# IPM_24V_12V.net
KiCad netlist of a schematic drawn in EasyEDA Pro
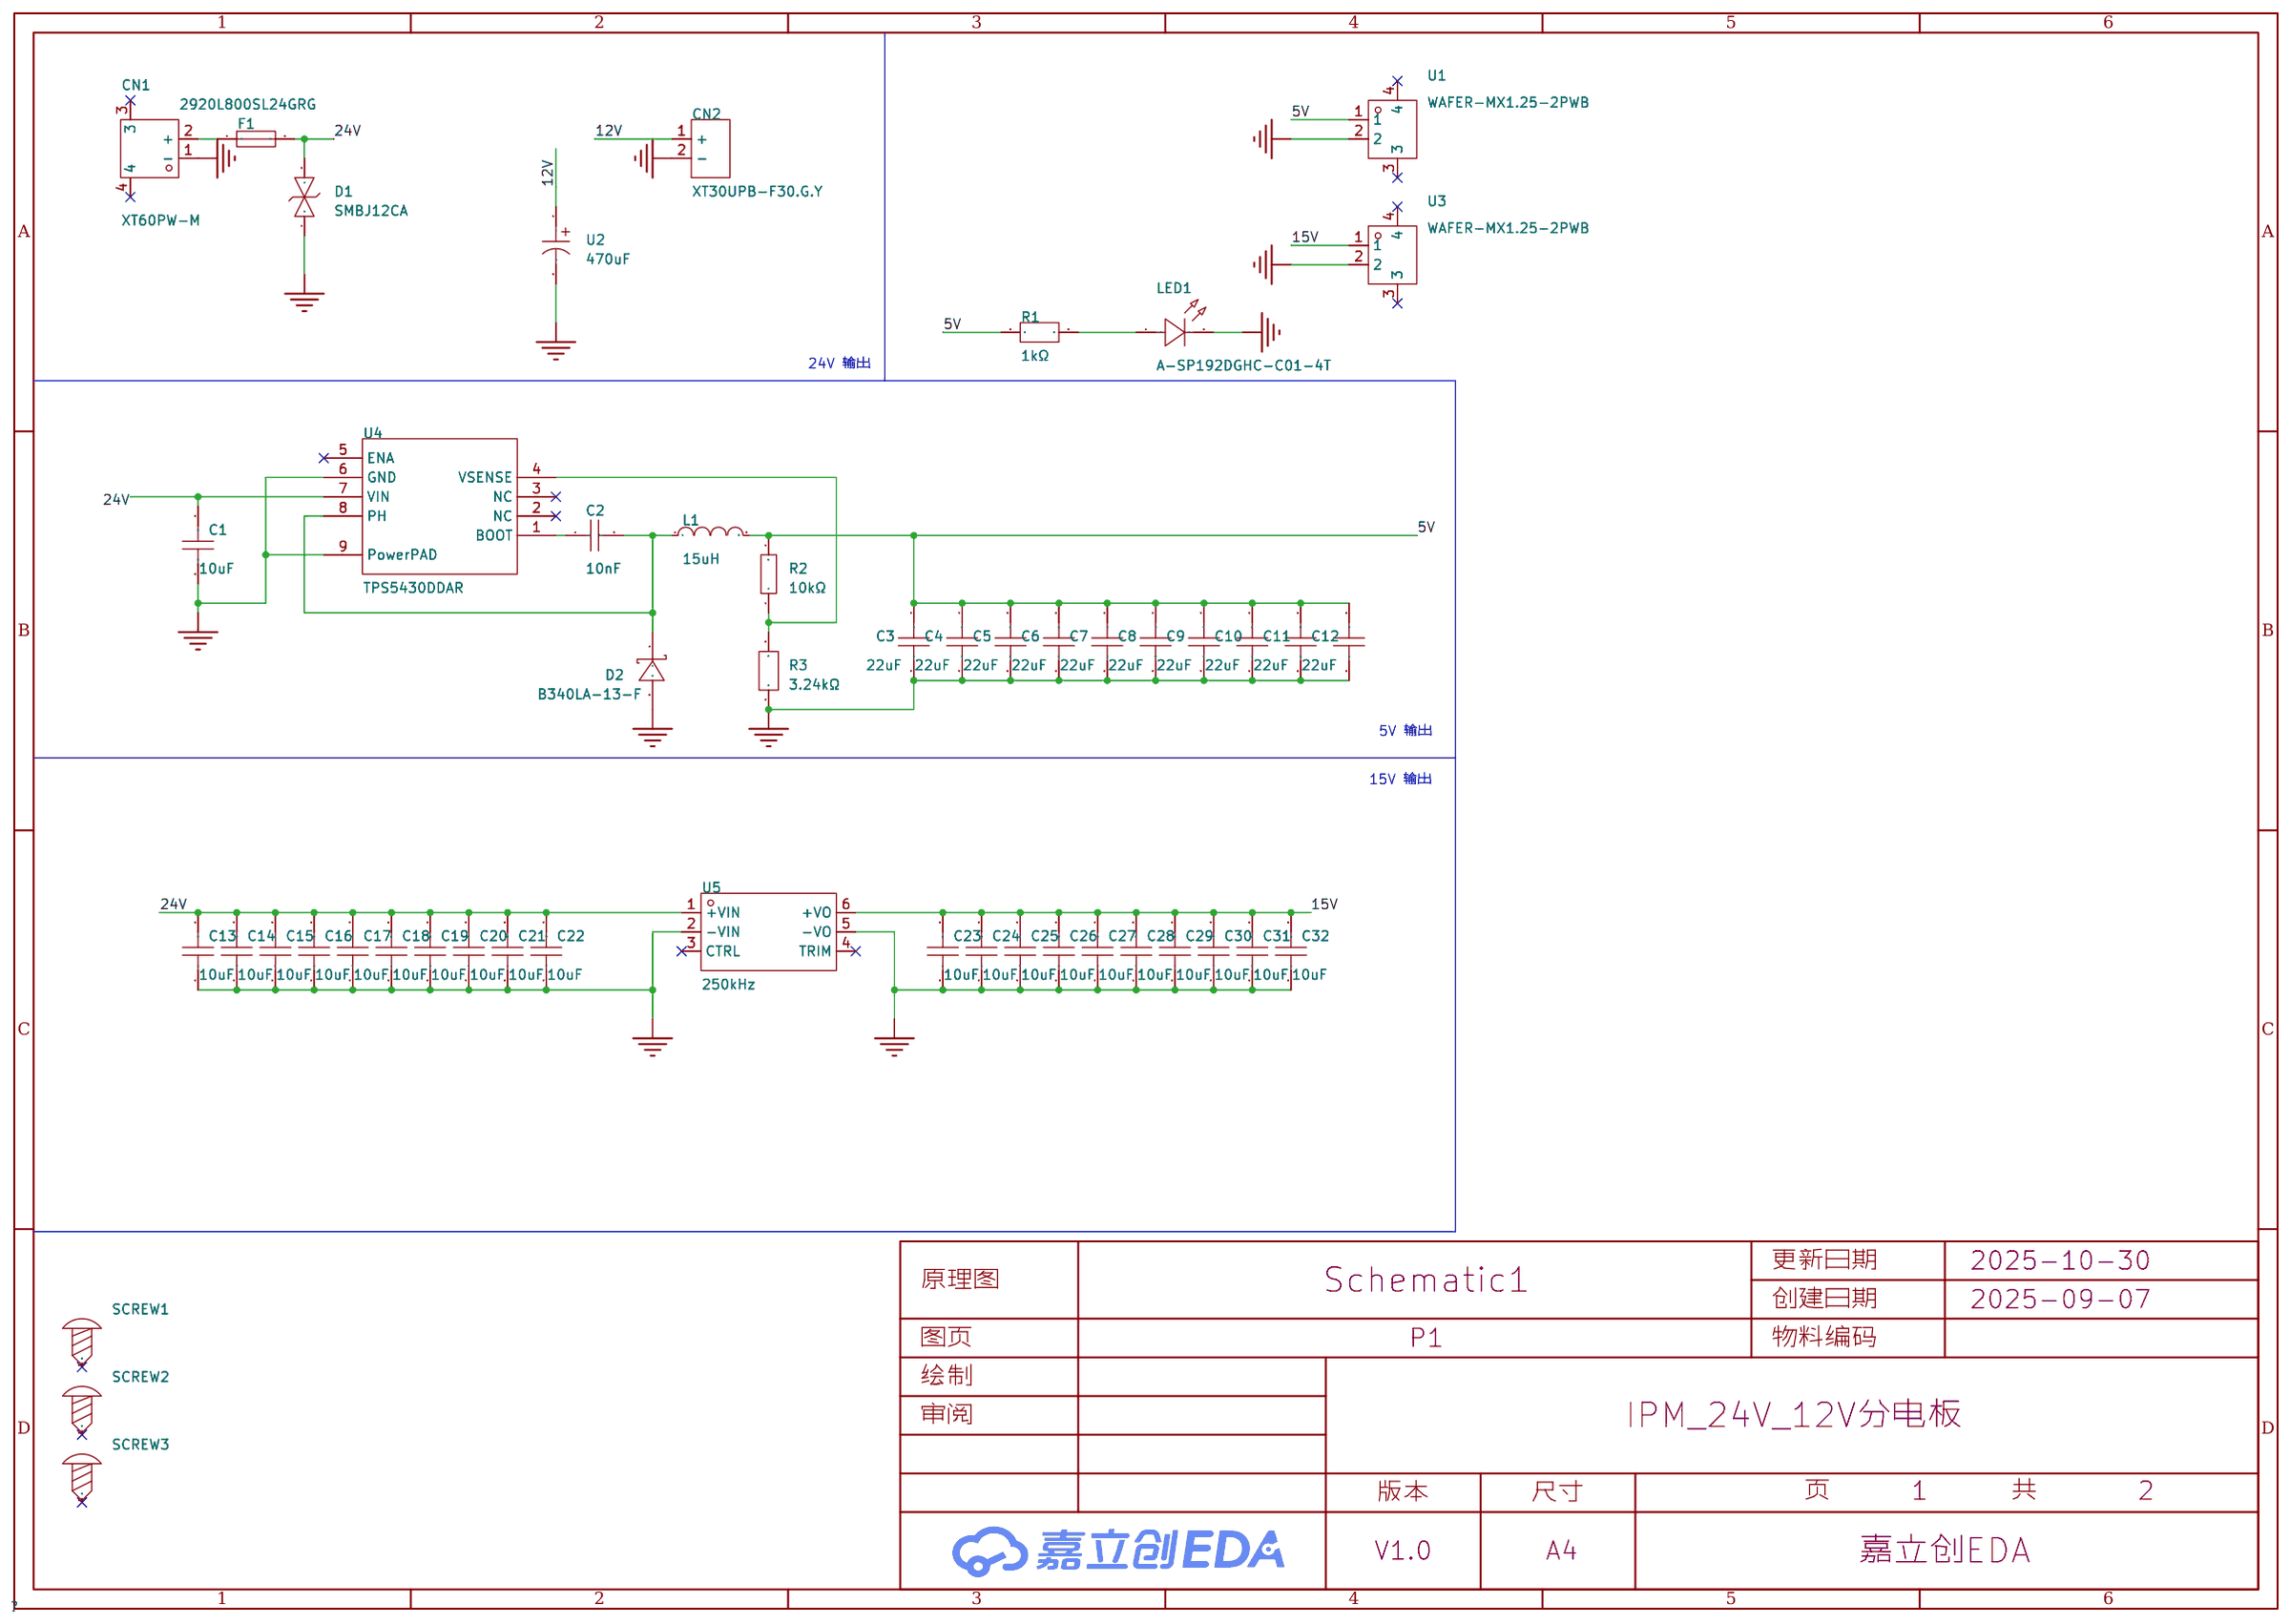
[diagram p0: P1]
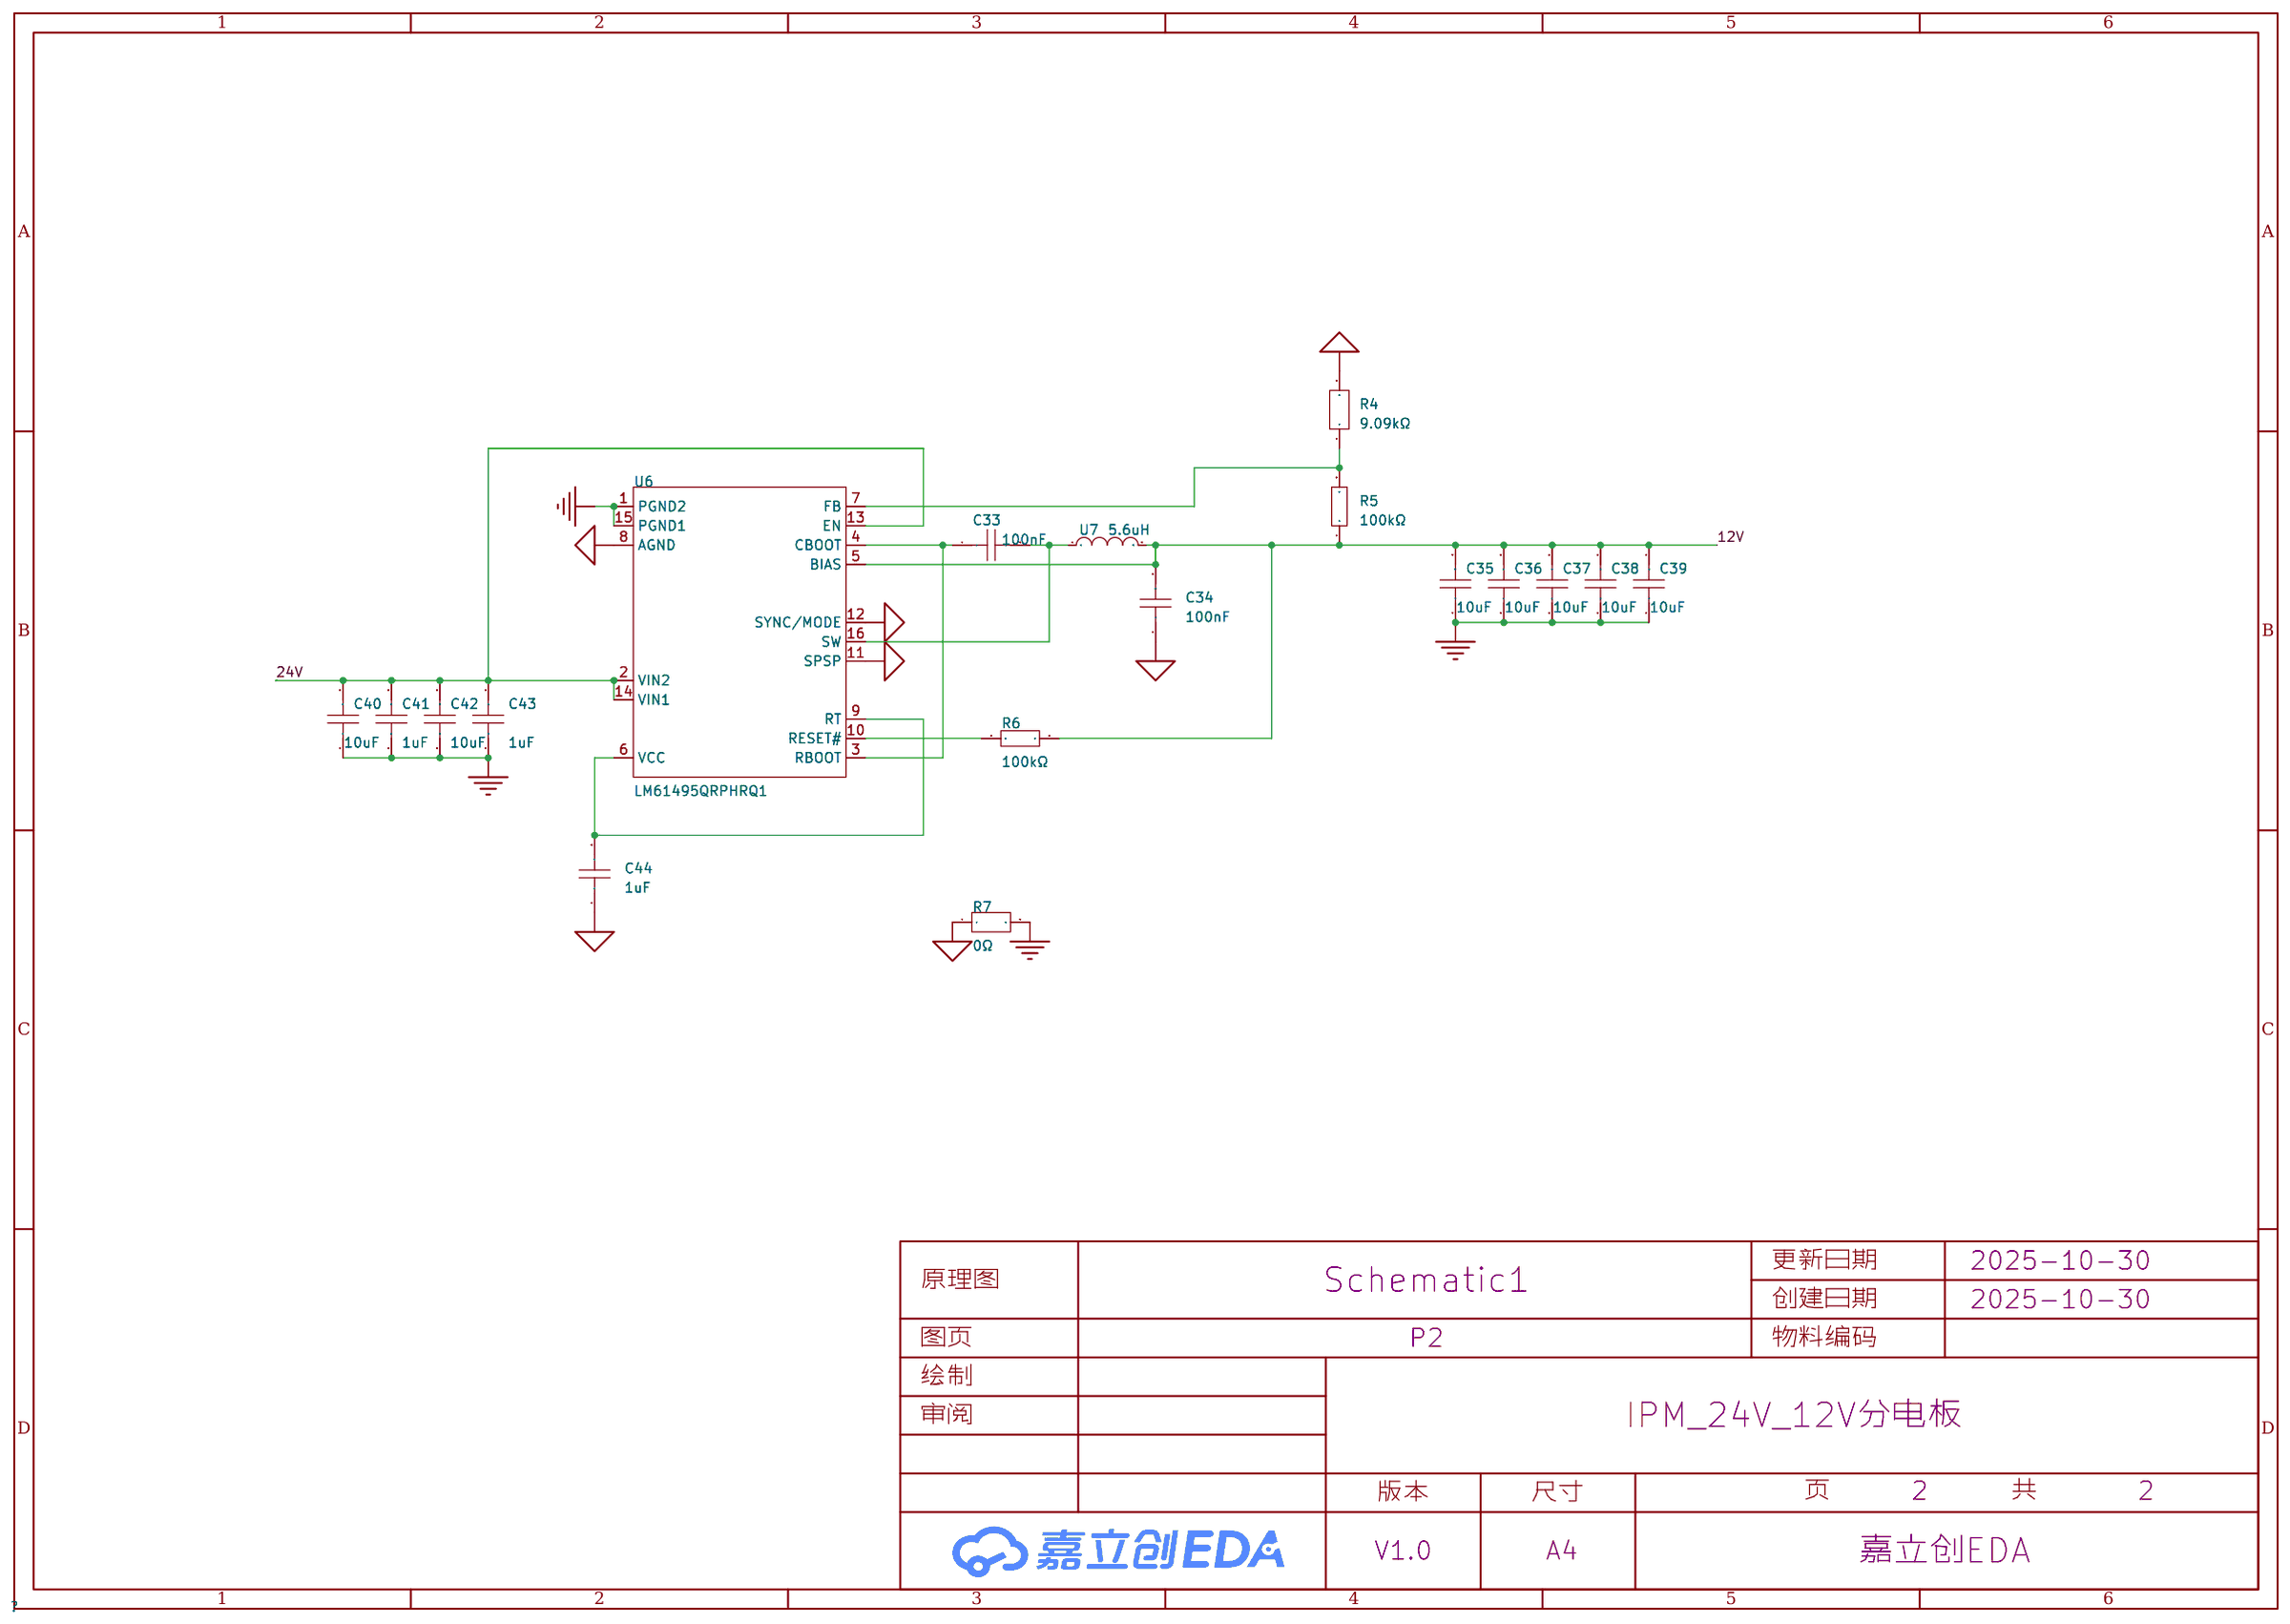
[diagram p1: P2]

(export (version "E")
  (design (tool "Eeschema 10.0.6"))
  (components
    (comp (ref "C1")
      (value "10uF")
      (footprint "easyedapro:C1206")
      (description "容值:10uF;精度:±10%;额定电压:50V;温度系数:X7R;")
      (fields
        (field (name "Manufacturer Part") "CL31B106KBHNNNE")
        (field (name "Manufacturer") "SAMSUNG(三星)")
      )
      (libsource (lib "easyedapro") (part "CL31B106KBHNNNE"))
    )
    (comp (ref "C2")
      (value "10nF")
      (footprint "easyedapro:C0603")
      (description "容值:10nF;精度:±10%;额定电压:50V;温度系数:X7R;")
      (fields
        (field (name "Manufacturer Part") "CL10B103KB8NNNC")
        (field (name "Manufacturer") "SAMSUNG(三星)")
      )
      (libsource (lib "easyedapro") (part "CL10B103KB8NNNC"))
    )
    (comp (ref "C3")
      (value "22uF")
      (footprint "easyedapro:C0603")
      (description "容值:22uF;精度:±20%;额定电压:16V;温度系数:X5R;")
      (fields
        (field (name "Manufacturer Part") "CL10A226MO7JZNC")
        (field (name "Manufacturer") "SAMSUNG(三星)")
      )
      (libsource (lib "easyedapro") (part "CL10A226MO7JZNC"))
    )
    (comp (ref "C4")
      (value "22uF")
      (footprint "easyedapro:C0603")
      (description "容值:22uF;精度:±20%;额定电压:16V;温度系数:X5R;")
      (fields
        (field (name "Manufacturer Part") "CL10A226MO7JZNC")
        (field (name "Manufacturer") "SAMSUNG(三星)")
      )
      (libsource (lib "easyedapro") (part "CL10A226MO7JZNC"))
    )
    (comp (ref "C5")
      (value "22uF")
      (footprint "easyedapro:C0603")
      (description "容值:22uF;精度:±20%;额定电压:16V;温度系数:X5R;")
      (fields
        (field (name "Manufacturer Part") "CL10A226MO7JZNC")
        (field (name "Manufacturer") "SAMSUNG(三星)")
      )
      (libsource (lib "easyedapro") (part "CL10A226MO7JZNC"))
    )
    (comp (ref "C6")
      (value "22uF")
      (footprint "easyedapro:C0603")
      (description "容值:22uF;精度:±20%;额定电压:16V;温度系数:X5R;")
      (fields
        (field (name "Manufacturer Part") "CL10A226MO7JZNC")
        (field (name "Manufacturer") "SAMSUNG(三星)")
      )
      (libsource (lib "easyedapro") (part "CL10A226MO7JZNC"))
    )
    (comp (ref "C7")
      (value "22uF")
      (footprint "easyedapro:C0603")
      (description "容值:22uF;精度:±20%;额定电压:16V;温度系数:X5R;")
      (fields
        (field (name "Manufacturer Part") "CL10A226MO7JZNC")
        (field (name "Manufacturer") "SAMSUNG(三星)")
      )
      (libsource (lib "easyedapro") (part "CL10A226MO7JZNC"))
    )
    (comp (ref "C8")
      (value "22uF")
      (footprint "easyedapro:C0603")
      (description "容值:22uF;精度:±20%;额定电压:16V;温度系数:X5R;")
      (fields
        (field (name "Manufacturer Part") "CL10A226MO7JZNC")
        (field (name "Manufacturer") "SAMSUNG(三星)")
      )
      (libsource (lib "easyedapro") (part "CL10A226MO7JZNC"))
    )
    (comp (ref "C9")
      (value "22uF")
      (footprint "easyedapro:C0603")
      (description "容值:22uF;精度:±20%;额定电压:16V;温度系数:X5R;")
      (fields
        (field (name "Manufacturer Part") "CL10A226MO7JZNC")
        (field (name "Manufacturer") "SAMSUNG(三星)")
      )
      (libsource (lib "easyedapro") (part "CL10A226MO7JZNC"))
    )
    (comp (ref "C10")
      (value "22uF")
      (footprint "easyedapro:C0603")
      (description "容值:22uF;精度:±20%;额定电压:16V;温度系数:X5R;")
      (fields
        (field (name "Manufacturer Part") "CL10A226MO7JZNC")
        (field (name "Manufacturer") "SAMSUNG(三星)")
      )
      (libsource (lib "easyedapro") (part "CL10A226MO7JZNC"))
    )
    (comp (ref "C11")
      (value "22uF")
      (footprint "easyedapro:C0603")
      (description "容值:22uF;精度:±20%;额定电压:16V;温度系数:X5R;")
      (fields
        (field (name "Manufacturer Part") "CL10A226MO7JZNC")
        (field (name "Manufacturer") "SAMSUNG(三星)")
      )
      (libsource (lib "easyedapro") (part "CL10A226MO7JZNC"))
    )
    (comp (ref "C12")
      (value "22uF")
      (footprint "easyedapro:C0603")
      (description "容值:22uF;精度:±20%;额定电压:16V;温度系数:X5R;")
      (fields
        (field (name "Manufacturer Part") "CL10A226MO7JZNC")
        (field (name "Manufacturer") "SAMSUNG(三星)")
      )
      (libsource (lib "easyedapro") (part "CL10A226MO7JZNC"))
    )
    (comp (ref "C13")
      (value "10uF")
      (footprint "easyedapro:C1206")
      (description "容值:10uF;精度:±10%;额定电压:50V;温度系数:X7R;")
      (fields
        (field (name "Manufacturer Part") "CL31B106KBHNNNE")
        (field (name "Manufacturer") "SAMSUNG(三星)")
      )
      (libsource (lib "easyedapro") (part "CL31B106KBHNNNE"))
    )
    (comp (ref "C14")
      (value "10uF")
      (footprint "easyedapro:C1206")
      (description "容值:10uF;精度:±10%;额定电压:50V;温度系数:X7R;")
      (fields
        (field (name "Manufacturer Part") "CL31B106KBHNNNE")
        (field (name "Manufacturer") "SAMSUNG(三星)")
      )
      (libsource (lib "easyedapro") (part "CL31B106KBHNNNE"))
    )
    (comp (ref "C15")
      (value "10uF")
      (footprint "easyedapro:C1206")
      (description "容值:10uF;精度:±10%;额定电压:50V;温度系数:X7R;")
      (fields
        (field (name "Manufacturer Part") "CL31B106KBHNNNE")
        (field (name "Manufacturer") "SAMSUNG(三星)")
      )
      (libsource (lib "easyedapro") (part "CL31B106KBHNNNE"))
    )
    (comp (ref "C16")
      (value "10uF")
      (footprint "easyedapro:C1206")
      (description "容值:10uF;精度:±10%;额定电压:50V;温度系数:X7R;")
      (fields
        (field (name "Manufacturer Part") "CL31B106KBHNNNE")
        (field (name "Manufacturer") "SAMSUNG(三星)")
      )
      (libsource (lib "easyedapro") (part "CL31B106KBHNNNE"))
    )
    (comp (ref "C17")
      (value "10uF")
      (footprint "easyedapro:C1206")
      (description "容值:10uF;精度:±10%;额定电压:50V;温度系数:X7R;")
      (fields
        (field (name "Manufacturer Part") "CL31B106KBHNNNE")
        (field (name "Manufacturer") "SAMSUNG(三星)")
      )
      (libsource (lib "easyedapro") (part "CL31B106KBHNNNE"))
    )
    (comp (ref "C18")
      (value "10uF")
      (footprint "easyedapro:C1206")
      (description "容值:10uF;精度:±10%;额定电压:50V;温度系数:X7R;")
      (fields
        (field (name "Manufacturer Part") "CL31B106KBHNNNE")
        (field (name "Manufacturer") "SAMSUNG(三星)")
      )
      (libsource (lib "easyedapro") (part "CL31B106KBHNNNE"))
    )
    (comp (ref "C19")
      (value "10uF")
      (footprint "easyedapro:C1206")
      (description "容值:10uF;精度:±10%;额定电压:50V;温度系数:X7R;")
      (fields
        (field (name "Manufacturer Part") "CL31B106KBHNNNE")
        (field (name "Manufacturer") "SAMSUNG(三星)")
      )
      (libsource (lib "easyedapro") (part "CL31B106KBHNNNE"))
    )
    (comp (ref "C20")
      (value "10uF")
      (footprint "easyedapro:C1206")
      (description "容值:10uF;精度:±10%;额定电压:50V;温度系数:X7R;")
      (fields
        (field (name "Manufacturer Part") "CL31B106KBHNNNE")
        (field (name "Manufacturer") "SAMSUNG(三星)")
      )
      (libsource (lib "easyedapro") (part "CL31B106KBHNNNE"))
    )
    (comp (ref "C21")
      (value "10uF")
      (footprint "easyedapro:C1206")
      (description "容值:10uF;精度:±10%;额定电压:50V;温度系数:X7R;")
      (fields
        (field (name "Manufacturer Part") "CL31B106KBHNNNE")
        (field (name "Manufacturer") "SAMSUNG(三星)")
      )
      (libsource (lib "easyedapro") (part "CL31B106KBHNNNE"))
    )
    (comp (ref "C22")
      (value "10uF")
      (footprint "easyedapro:C1206")
      (description "容值:10uF;精度:±10%;额定电压:50V;温度系数:X7R;")
      (fields
        (field (name "Manufacturer Part") "CL31B106KBHNNNE")
        (field (name "Manufacturer") "SAMSUNG(三星)")
      )
      (libsource (lib "easyedapro") (part "CL31B106KBHNNNE"))
    )
    (comp (ref "C23")
      (value "10uF")
      (footprint "easyedapro:C1206")
      (description "容值:10uF;精度:±10%;额定电压:50V;温度系数:X7R;")
      (fields
        (field (name "Manufacturer Part") "CL31B106KBHNNNE")
        (field (name "Manufacturer") "SAMSUNG(三星)")
      )
      (libsource (lib "easyedapro") (part "CL31B106KBHNNNE"))
    )
    (comp (ref "C24")
      (value "10uF")
      (footprint "easyedapro:C1206")
      (description "容值:10uF;精度:±10%;额定电压:50V;温度系数:X7R;")
      (fields
        (field (name "Manufacturer Part") "CL31B106KBHNNNE")
        (field (name "Manufacturer") "SAMSUNG(三星)")
      )
      (libsource (lib "easyedapro") (part "CL31B106KBHNNNE"))
    )
    (comp (ref "C25")
      (value "10uF")
      (footprint "easyedapro:C1206")
      (description "容值:10uF;精度:±10%;额定电压:50V;温度系数:X7R;")
      (fields
        (field (name "Manufacturer Part") "CL31B106KBHNNNE")
        (field (name "Manufacturer") "SAMSUNG(三星)")
      )
      (libsource (lib "easyedapro") (part "CL31B106KBHNNNE"))
    )
    (comp (ref "C26")
      (value "10uF")
      (footprint "easyedapro:C1206")
      (description "容值:10uF;精度:±10%;额定电压:50V;温度系数:X7R;")
      (fields
        (field (name "Manufacturer Part") "CL31B106KBHNNNE")
        (field (name "Manufacturer") "SAMSUNG(三星)")
      )
      (libsource (lib "easyedapro") (part "CL31B106KBHNNNE"))
    )
    (comp (ref "C27")
      (value "10uF")
      (footprint "easyedapro:C1206")
      (description "容值:10uF;精度:±10%;额定电压:50V;温度系数:X7R;")
      (fields
        (field (name "Manufacturer Part") "CL31B106KBHNNNE")
        (field (name "Manufacturer") "SAMSUNG(三星)")
      )
      (libsource (lib "easyedapro") (part "CL31B106KBHNNNE"))
    )
    (comp (ref "C28")
      (value "10uF")
      (footprint "easyedapro:C1206")
      (description "容值:10uF;精度:±10%;额定电压:50V;温度系数:X7R;")
      (fields
        (field (name "Manufacturer Part") "CL31B106KBHNNNE")
        (field (name "Manufacturer") "SAMSUNG(三星)")
      )
      (libsource (lib "easyedapro") (part "CL31B106KBHNNNE"))
    )
    (comp (ref "C29")
      (value "10uF")
      (footprint "easyedapro:C1206")
      (description "容值:10uF;精度:±10%;额定电压:50V;温度系数:X7R;")
      (fields
        (field (name "Manufacturer Part") "CL31B106KBHNNNE")
        (field (name "Manufacturer") "SAMSUNG(三星)")
      )
      (libsource (lib "easyedapro") (part "CL31B106KBHNNNE"))
    )
    (comp (ref "C30")
      (value "10uF")
      (footprint "easyedapro:C1206")
      (description "容值:10uF;精度:±10%;额定电压:50V;温度系数:X7R;")
      (fields
        (field (name "Manufacturer Part") "CL31B106KBHNNNE")
        (field (name "Manufacturer") "SAMSUNG(三星)")
      )
      (libsource (lib "easyedapro") (part "CL31B106KBHNNNE"))
    )
    (comp (ref "C31")
      (value "10uF")
      (footprint "easyedapro:C1206")
      (description "容值:10uF;精度:±10%;额定电压:50V;温度系数:X7R;")
      (fields
        (field (name "Manufacturer Part") "CL31B106KBHNNNE")
        (field (name "Manufacturer") "SAMSUNG(三星)")
      )
      (libsource (lib "easyedapro") (part "CL31B106KBHNNNE"))
    )
    (comp (ref "C32")
      (value "10uF")
      (footprint "easyedapro:C1206")
      (description "容值:10uF;精度:±10%;额定电压:50V;温度系数:X7R;")
      (fields
        (field (name "Manufacturer Part") "CL31B106KBHNNNE")
        (field (name "Manufacturer") "SAMSUNG(三星)")
      )
      (libsource (lib "easyedapro") (part "CL31B106KBHNNNE"))
    )
    (comp (ref "CN1")
      (value "XT60PW-M")
      (footprint "easyedapro:CONN-TH_XT60PW-M")
      (description "类别:-;类型1:-;")
      (fields (field (name "Manufacturer") "AMASS(艾迈斯)"))
      (libsource (lib "easyedapro") (part "XT60PW-M"))
    )
    (comp (ref "CN2")
      (value "XT30UPB-F30.G.Y")
      (footprint "easyedapro:CONN-TH_XT30UPB-F")
      (description "类别:-;类型1:-;")
      (fields (field (name "Manufacturer") "AMASS(艾迈斯)"))
      (libsource (lib "easyedapro") (part "XT30UPB-F"))
    )
    (comp (ref "D1")
      (value "SMBJ12CA")
      (footprint "easyedapro:SMB_L4.6-W3.6-LS5.4-BI")
      (fields (field (name "Manufacturer") "R+O(宏嘉诚)"))
      (libsource (lib "easyedapro") (part "SMBJ12CA_C19077566"))
    )
    (comp (ref "D2")
      (value "B340LA-13-F")
      (footprint "easyedapro:SMA_L4.3-W2.6-LS5.2-RD")
      (description "正向压降(Vf):450mV@3A;直流反向耐压(Vr):40V;平均整流电流(Io):3A;")
      (fields (field (name "Manufacturer") "DIODES(美台)"))
      (libsource (lib "easyedapro") (part "B340LA-13-F"))
    )
    (comp (ref "F1")
      (value "2920L800SL24GRG")
      (footprint "easyedapro:F2920")
      (description "耐压(Vmax):24V;最大电流(Imax):50A;保持电流(Ihold):8A;跳闸电流(Itrip):16A;")
      (fields (field (name "Manufacturer") "LUTE(陆特)"))
      (libsource (lib "easyedapro") (part "2920L800SL24GRG"))
    )
    (comp (ref "L1")
      (value "15uH")
      (footprint "easyedapro:IND-SMD_L7.0-W6.6_FXL0630")
      (description "电感值:15uH;精度:±20%;额定电流:3A;饱和电流(Isat):4A;类型:一体成型电感;")
      (fields (field (name "Manufacturer Part") "FXL0630-150-M") (field (name "Manufacturer") "cjiang(长江微电)"))
      (libsource (lib "easyedapro") (part "FXL0630-150-M"))
    )
    (comp (ref "LED1")
      (value "A-SP192DGHC-C01-4T")
      (footprint "easyedapro:LED0603-FD")
      (fields (field (name "Manufacturer") "Amicc(欧密格光电)"))
      (libsource (lib "easyedapro") (part "A-SP192DGHC-C01-4T"))
    )
    (comp (ref "R1")
      (value "1kΩ")
      (footprint "easyedapro:R0603")
      (description "电阻类型:厚膜电阻;阻值:1kΩ;精度:±1%;功率:100mW;工作电压:75V;温度系数:±100ppm/°C;")
      (fields (field (name "Manufacturer Part") "FRC0603F1001TS") (field (name "Manufacturer") "FOJAN(富捷)"))
      (libsource (lib "easyedapro") (part "FRC0603F1001TS"))
    )
    (comp (ref "R2")
      (value "10kΩ")
      (footprint "easyedapro:R0603")
      (description "电阻类型:厚膜电阻;阻值:10kΩ;精度:±1%;功率:100mW;工作电压:75V;温度系数:±100ppm/°C;")
      (fields
        (field (name "Manufacturer Part") "0603WAF1002T5E")
        (field (name "Manufacturer") "UNI-ROYAL(厚声)")
      )
      (libsource (lib "easyedapro") (part "0603WAF1002T5E"))
    )
    (comp (ref "R3")
      (value "3.24kΩ")
      (footprint "easyedapro:R0603")
      (description "电阻类型:厚膜电阻;阻值:3.24kΩ;精度:±1%;功率:100mW;工作电压:75V;温度系数:±100ppm/°C;")
      (fields (field (name "Manufacturer Part") "FRC0603F3241TS") (field (name "Manufacturer") "FOJAN(富捷)"))
      (libsource (lib "easyedapro") (part "FRC0603F3241TS"))
    )
    (comp (ref "SCREW1")
      (value "~")
      (footprint "easyedapro:M2螺丝")
      (libsource (lib "easyedapro") (part "螺丝孔"))
    )
    (comp (ref "SCREW2")
      (value "~")
      (footprint "easyedapro:M2螺丝")
      (libsource (lib "easyedapro") (part "螺丝孔"))
    )
    (comp (ref "SCREW3")
      (value "~")
      (footprint "easyedapro:M2螺丝")
      (libsource (lib "easyedapro") (part "螺丝孔"))
    )
    (comp (ref "U1")
      (value "WAFER-MX1.25-2PWB")
      (footprint "easyedapro:CONN-SMD_2P-P1.25_XUNPU_WAFER-MX1.25-2PWB")
      (fields (field (name "Manufacturer") "XUNPU(讯普)"))
      (libsource (lib "easyedapro") (part "WAFER-MX1.25-2PWB"))
    )
    (comp (ref "U2")
      (value "470uF")
      (footprint "easyedapro:CAP-TH_BD10.0-P5.00-D1.0-FD")
      (description "容值:470uF;精度:±20%;额定电压:50V;纹波电流:-;等效串联电阻(ESR):-;")
      (fields
        (field (name "Manufacturer Part") "ERJ1HM471G16C36T")
        (field (name "Manufacturer") "AISHI(艾华集团)")
      )
      (libsource (lib "easyedapro") (part "ERJ1HM471G16C36T"))
    )
    (comp (ref "U3")
      (value "WAFER-MX1.25-2PWB")
      (footprint "easyedapro:CONN-SMD_2P-P1.25_XUNPU_WAFER-MX1.25-2PWB")
      (fields (field (name "Manufacturer") "XUNPU(讯普)"))
      (libsource (lib "easyedapro") (part "WAFER-MX1.25-2PWB"))
    )
    (comp (ref "U4")
      (value "TPS5430DDAR")
      (footprint "easyedapro:ESOP-8_L4.9-W3.9-P1.27-LS6.0-TL-EP")
      (description "功能类型:降压型;输出类型:可调;工作电压:5.5V~36V;输出电压:1.221V~32.04V;输出电流:3A;")
      (fields (field (name "Manufacturer") "TI(德州仪器)"))
      (libsource (lib "easyedapro") (part "TPS5430DDAR"))
    )
    (comp (ref "U5")
      (value "250kHz")
      (footprint "easyedapro:PWRM-TH_URB2415LD-30WR3")
      (fields (field (name "Manufacturer Part") "URB2415LD-30WR3") (field (name "Manufacturer") "YLPTEC(易川)"))
      (libsource (lib "easyedapro") (part "URB2415LD-30WR3_C5369835"))
    )
    (comp (ref "C33")
      (value "100nF")
      (footprint "easyedapro:C0603")
      (description "容值:100nF;精度:±10%;额定电压:50V;温度系数:X7R;")
      (fields
        (field (name "Manufacturer Part") "CC0603KRX7R9BB104")
        (field (name "Manufacturer") "YAGEO(国巨)")
      )
      (libsource (lib "easyedapro") (part "CC0603KRX7R9BB104"))
    )
    (comp (ref "C34")
      (value "100nF")
      (footprint "easyedapro:C0603")
      (description "容值:100nF;精度:±10%;额定电压:50V;温度系数:X7R;")
      (fields
        (field (name "Manufacturer Part") "CC0603KRX7R9BB104")
        (field (name "Manufacturer") "YAGEO(国巨)")
      )
      (libsource (lib "easyedapro") (part "CC0603KRX7R9BB104"))
    )
    (comp (ref "C35")
      (value "10uF")
      (footprint "easyedapro:C1206")
      (description "容值:10uF;精度:±10%;额定电压:50V;温度系数:X7R;")
      (fields
        (field (name "Manufacturer Part") "CL31B106KBHNNNE")
        (field (name "Manufacturer") "SAMSUNG(三星)")
      )
      (libsource (lib "easyedapro") (part "CL31B106KBHNNNE"))
    )
    (comp (ref "C36")
      (value "10uF")
      (footprint "easyedapro:C1206")
      (description "容值:10uF;精度:±10%;额定电压:50V;温度系数:X7R;")
      (fields
        (field (name "Manufacturer Part") "CL31B106KBHNNNE")
        (field (name "Manufacturer") "SAMSUNG(三星)")
      )
      (libsource (lib "easyedapro") (part "CL31B106KBHNNNE"))
    )
    (comp (ref "C37")
      (value "10uF")
      (footprint "easyedapro:C1206")
      (description "容值:10uF;精度:±10%;额定电压:50V;温度系数:X7R;")
      (fields
        (field (name "Manufacturer Part") "CL31B106KBHNNNE")
        (field (name "Manufacturer") "SAMSUNG(三星)")
      )
      (libsource (lib "easyedapro") (part "CL31B106KBHNNNE"))
    )
    (comp (ref "C38")
      (value "10uF")
      (footprint "easyedapro:C1206")
      (description "容值:10uF;精度:±10%;额定电压:50V;温度系数:X7R;")
      (fields
        (field (name "Manufacturer Part") "CL31B106KBHNNNE")
        (field (name "Manufacturer") "SAMSUNG(三星)")
      )
      (libsource (lib "easyedapro") (part "CL31B106KBHNNNE"))
    )
    (comp (ref "C39")
      (value "10uF")
      (footprint "easyedapro:C1206")
      (description "容值:10uF;精度:±10%;额定电压:50V;温度系数:X7R;")
      (fields
        (field (name "Manufacturer Part") "CL31B106KBHNNNE")
        (field (name "Manufacturer") "SAMSUNG(三星)")
      )
      (libsource (lib "easyedapro") (part "CL31B106KBHNNNE"))
    )
    (comp (ref "C40")
      (value "10uF")
      (footprint "easyedapro:C1206")
      (description "容值:10uF;精度:±10%;额定电压:50V;温度系数:X7R;")
      (fields
        (field (name "Manufacturer Part") "CL31B106KBHNNNE")
        (field (name "Manufacturer") "SAMSUNG(三星)")
      )
      (libsource (lib "easyedapro") (part "CL31B106KBHNNNE"))
    )
    (comp (ref "C41")
      (value "1uF")
      (footprint "easyedapro:C1206")
      (description "容值:1uF;精度:±10%;额定电压:50V;温度系数:X7R;")
      (fields
        (field (name "Manufacturer Part") "CL31B105KBHNNNE")
        (field (name "Manufacturer") "SAMSUNG(三星)")
      )
      (libsource (lib "easyedapro") (part "CL31B105KBHNNNE"))
    )
    (comp (ref "C42")
      (value "10uF")
      (footprint "easyedapro:C1206")
      (description "容值:10uF;精度:±10%;额定电压:50V;温度系数:X7R;")
      (fields
        (field (name "Manufacturer Part") "CL31B106KBHNNNE")
        (field (name "Manufacturer") "SAMSUNG(三星)")
      )
      (libsource (lib "easyedapro") (part "CL31B106KBHNNNE"))
    )
    (comp (ref "C43")
      (value "1uF")
      (footprint "easyedapro:C1206")
      (description "容值:1uF;精度:±10%;额定电压:50V;温度系数:X7R;")
      (fields
        (field (name "Manufacturer Part") "CL31B105KBHNNNE")
        (field (name "Manufacturer") "SAMSUNG(三星)")
      )
      (libsource (lib "easyedapro") (part "CL31B105KBHNNNE"))
    )
    (comp (ref "C44")
      (value "1uF")
      (footprint "easyedapro:C0603")
      (description "容值:1uF;精度:±10%;额定电压:50V;温度系数:X5R;")
      (fields
        (field (name "Manufacturer Part") "CL10A105KB8NNNC")
        (field (name "Manufacturer") "SAMSUNG(三星)")
      )
      (libsource (lib "easyedapro") (part "CL10A105KB8NNNC"))
    )
    (comp (ref "R4")
      (value "9.09kΩ")
      (footprint "easyedapro:R0603")
      (description "电阻类型:薄膜电阻;阻值:9.09kΩ;精度:±0.1%;功率:100mW;温度系数:±25ppm/°C;")
      (fields (field (name "Manufacturer Part") "RT0603BRD079K09L") (field (name "Manufacturer") "YAGEO(国巨)"))
      (libsource (lib "easyedapro") (part "RT0603BRD079K09L"))
    )
    (comp (ref "R5")
      (value "100kΩ")
      (footprint "easyedapro:R0603")
      (description "电阻类型:厚膜电阻;阻值:100kΩ;精度:±1%;功率:100mW;工作电压:75V;温度系数:±100ppm/°C;")
      (fields
        (field (name "Manufacturer Part") "0603WAF1003T5E")
        (field (name "Manufacturer") "UNI-ROYAL(厚声)")
      )
      (libsource (lib "easyedapro") (part "0603WAF1003T5E"))
    )
    (comp (ref "R6")
      (value "100kΩ")
      (footprint "easyedapro:R0603")
      (description "电阻类型:厚膜电阻;阻值:100kΩ;精度:±1%;功率:100mW;工作电压:75V;温度系数:±100ppm/°C;")
      (fields
        (field (name "Manufacturer Part") "0603WAF1003T5E")
        (field (name "Manufacturer") "UNI-ROYAL(厚声)")
      )
      (libsource (lib "easyedapro") (part "0603WAF1003T5E"))
    )
    (comp (ref "R7")
      (value "0Ω")
      (footprint "easyedapro:R1206")
      (description "电阻类型:采样电阻；合金电阻;阻值:0Ω;精度:±1%;功率:1W;")
      (fields (field (name "Manufacturer Part") "RE1206F1R000") (field (name "Manufacturer") "JIERR(捷而瑞)"))
      (libsource (lib "easyedapro") (part "RE1206F1R000"))
    )
    (comp (ref "U6")
      (value "LM61495QRPHRQ1")
      (footprint "easyedapro:VQFN-16_L4.5-W3.5-P0.50-TL_TI_RPH")
      (description "功能类型:降压型;工作电压:3V~36V;输出电压:1V~34.2V;输出电流:10A;输出类型:可调;")
      (fields (field (name "Manufacturer") "TI(德州仪器)"))
      (libsource (lib "easyedapro") (part "LM61495QRPHRQ1"))
    )
    (comp (ref "U7")
      (value "5.6uH")
      (footprint "easyedapro:IND-SMD_L6.6-W6.4")
      (description "电感值:5.6uH;精度:±20%;额定电流:10A;饱和电流(Isat):9.9A;类型:-;")
      (fields
        (field (name "Manufacturer Part") "FEXL0660A-5R6M")
        (field (name "Manufacturer") "cjiang(长江微电)")
      )
      (libsource (lib "easyedapro") (part "FEXL0660A-5R6M"))
    )
  )
  (nets
    (net (code "1") (name "5V") (class "Default")
      (node (ref "C10") (pin "1") (pinfunction "1_1") (pintype "unspecified"))
      (node (ref "C11") (pin "1") (pinfunction "1_1") (pintype "unspecified"))
      (node (ref "C12") (pin "1") (pinfunction "1_1") (pintype "unspecified"))
      (node (ref "C3") (pin "1") (pinfunction "1_1") (pintype "unspecified"))
      (node (ref "C4") (pin "1") (pinfunction "1_1") (pintype "unspecified"))
      (node (ref "C5") (pin "1") (pinfunction "1_1") (pintype "unspecified"))
      (node (ref "C6") (pin "1") (pinfunction "1_1") (pintype "unspecified"))
      (node (ref "C7") (pin "1") (pinfunction "1_1") (pintype "unspecified"))
      (node (ref "C8") (pin "1") (pinfunction "1_1") (pintype "unspecified"))
      (node (ref "C9") (pin "1") (pinfunction "1_1") (pintype "unspecified"))
      (node (ref "L1") (pin "2") (pinfunction "2_2") (pintype "unspecified"))
      (node (ref "R1") (pin "1") (pinfunction "1_1") (pintype "unspecified"))
      (node (ref "R2") (pin "2") (pinfunction "2_2") (pintype "input"))
      (node (ref "U1") (pin "1") (pinfunction "1_1") (pintype "unspecified"))
    )
    (net (code "2") (name "12V") (class "Default")
      (node (ref "C34") (pin "2") (pinfunction "2_2") (pintype "unspecified"))
      (node (ref "C35") (pin "2") (pinfunction "2_2") (pintype "unspecified"))
      (node (ref "C36") (pin "2") (pinfunction "2_2") (pintype "unspecified"))
      (node (ref "C37") (pin "2") (pinfunction "2_2") (pintype "unspecified"))
      (node (ref "C38") (pin "2") (pinfunction "2_2") (pintype "unspecified"))
      (node (ref "C39") (pin "2") (pinfunction "2_2") (pintype "unspecified"))
      (node (ref "CN2") (pin "1") (pinfunction "+_1") (pintype "unspecified"))
      (node (ref "R5") (pin "1") (pinfunction "1_1") (pintype "input"))
      (node (ref "R6") (pin "2") (pinfunction "2_2") (pintype "input"))
      (node (ref "U2") (pin "1") (pinfunction "1_1") (pintype "input"))
      (node (ref "U6") (pin "5") (pinfunction "BIAS_5") (pintype "unspecified"))
      (node (ref "U7") (pin "2") (pinfunction "2_2") (pintype "unspecified"))
    )
    (net (code "3") (name "15V") (class "Default")
      (node (ref "C23") (pin "2") (pinfunction "2_2") (pintype "unspecified"))
      (node (ref "C24") (pin "2") (pinfunction "2_2") (pintype "unspecified"))
      (node (ref "C25") (pin "2") (pinfunction "2_2") (pintype "unspecified"))
      (node (ref "C26") (pin "2") (pinfunction "2_2") (pintype "unspecified"))
      (node (ref "C27") (pin "2") (pinfunction "2_2") (pintype "unspecified"))
      (node (ref "C28") (pin "2") (pinfunction "2_2") (pintype "unspecified"))
      (node (ref "C29") (pin "2") (pinfunction "2_2") (pintype "unspecified"))
      (node (ref "C30") (pin "2") (pinfunction "2_2") (pintype "unspecified"))
      (node (ref "C31") (pin "2") (pinfunction "2_2") (pintype "unspecified"))
      (node (ref "C32") (pin "2") (pinfunction "2_2") (pintype "unspecified"))
      (node (ref "U3") (pin "1") (pinfunction "1_1") (pintype "unspecified"))
      (node (ref "U5") (pin "6") (pinfunction "+VO_6") (pintype "unspecified"))
    )
    (net (code "4") (name "24V") (class "Default")
      (node (ref "C1") (pin "2") (pinfunction "2_2") (pintype "unspecified"))
      (node (ref "C13") (pin "2") (pinfunction "2_2") (pintype "unspecified"))
      (node (ref "C14") (pin "2") (pinfunction "2_2") (pintype "unspecified"))
      (node (ref "C15") (pin "2") (pinfunction "2_2") (pintype "unspecified"))
      (node (ref "C16") (pin "2") (pinfunction "2_2") (pintype "unspecified"))
      (node (ref "C17") (pin "2") (pinfunction "2_2") (pintype "unspecified"))
      (node (ref "C18") (pin "2") (pinfunction "2_2") (pintype "unspecified"))
      (node (ref "C19") (pin "2") (pinfunction "2_2") (pintype "unspecified"))
      (node (ref "C20") (pin "2") (pinfunction "2_2") (pintype "unspecified"))
      (node (ref "C21") (pin "2") (pinfunction "2_2") (pintype "unspecified"))
      (node (ref "C22") (pin "2") (pinfunction "2_2") (pintype "unspecified"))
      (node (ref "C40") (pin "2") (pinfunction "2_2") (pintype "unspecified"))
      (node (ref "C41") (pin "2") (pinfunction "2_2") (pintype "unspecified"))
      (node (ref "C42") (pin "2") (pinfunction "2_2") (pintype "unspecified"))
      (node (ref "C43") (pin "2") (pinfunction "2_2") (pintype "unspecified"))
      (node (ref "D1") (pin "2") (pinfunction "2_2") (pintype "unspecified"))
      (node (ref "F1") (pin "2") (pinfunction "2_2") (pintype "unspecified"))
      (node (ref "U4") (pin "7") (pinfunction "VIN_7") (pintype "unspecified"))
      (node (ref "U5") (pin "1") (pinfunction "+VIN_1") (pintype "unspecified"))
      (node (ref "U6") (pin "13") (pinfunction "EN_13") (pintype "unspecified"))
      (node (ref "U6") (pin "14") (pinfunction "VIN1_14") (pintype "unspecified"))
      (node (ref "U6") (pin "2") (pinfunction "VIN2_2") (pintype "unspecified"))
    )
    (net (code "5") (name "AGND") (class "Default")
      (node (ref "C34") (pin "1") (pinfunction "1_1") (pintype "unspecified"))
      (node (ref "C44") (pin "1") (pinfunction "1_1") (pintype "unspecified"))
      (node (ref "R4") (pin "2") (pinfunction "2_2") (pintype "unspecified"))
      (node (ref "R7") (pin "1") (pinfunction "1_1") (pintype "unspecified"))
      (node (ref "U6") (pin "11") (pinfunction "SPSP_11") (pintype "unspecified"))
      (node (ref "U6") (pin "12") (pinfunction "SYNC/MODE_12") (pintype "unspecified"))
      (node (ref "U6") (pin "8") (pinfunction "AGND_8") (pintype "unspecified"))
    )
    (net (code "6") (name "GND") (class "Default")
      (node (ref "C1") (pin "1") (pinfunction "1_1") (pintype "unspecified"))
      (node (ref "C10") (pin "2") (pinfunction "2_2") (pintype "unspecified"))
      (node (ref "C11") (pin "2") (pinfunction "2_2") (pintype "unspecified"))
      (node (ref "C12") (pin "2") (pinfunction "2_2") (pintype "unspecified"))
      (node (ref "C13") (pin "1") (pinfunction "1_1") (pintype "unspecified"))
      (node (ref "C14") (pin "1") (pinfunction "1_1") (pintype "unspecified"))
      (node (ref "C15") (pin "1") (pinfunction "1_1") (pintype "unspecified"))
      (node (ref "C16") (pin "1") (pinfunction "1_1") (pintype "unspecified"))
      (node (ref "C17") (pin "1") (pinfunction "1_1") (pintype "unspecified"))
      (node (ref "C18") (pin "1") (pinfunction "1_1") (pintype "unspecified"))
      (node (ref "C19") (pin "1") (pinfunction "1_1") (pintype "unspecified"))
      (node (ref "C20") (pin "1") (pinfunction "1_1") (pintype "unspecified"))
      (node (ref "C21") (pin "1") (pinfunction "1_1") (pintype "unspecified"))
      (node (ref "C22") (pin "1") (pinfunction "1_1") (pintype "unspecified"))
      (node (ref "C23") (pin "1") (pinfunction "1_1") (pintype "unspecified"))
      (node (ref "C24") (pin "1") (pinfunction "1_1") (pintype "unspecified"))
      (node (ref "C25") (pin "1") (pinfunction "1_1") (pintype "unspecified"))
      (node (ref "C26") (pin "1") (pinfunction "1_1") (pintype "unspecified"))
      (node (ref "C27") (pin "1") (pinfunction "1_1") (pintype "unspecified"))
      (node (ref "C28") (pin "1") (pinfunction "1_1") (pintype "unspecified"))
      (node (ref "C29") (pin "1") (pinfunction "1_1") (pintype "unspecified"))
      (node (ref "C3") (pin "2") (pinfunction "2_2") (pintype "unspecified"))
      (node (ref "C30") (pin "1") (pinfunction "1_1") (pintype "unspecified"))
      (node (ref "C31") (pin "1") (pinfunction "1_1") (pintype "unspecified"))
      (node (ref "C32") (pin "1") (pinfunction "1_1") (pintype "unspecified"))
      (node (ref "C35") (pin "1") (pinfunction "1_1") (pintype "unspecified"))
      (node (ref "C36") (pin "1") (pinfunction "1_1") (pintype "unspecified"))
      (node (ref "C37") (pin "1") (pinfunction "1_1") (pintype "unspecified"))
      (node (ref "C38") (pin "1") (pinfunction "1_1") (pintype "unspecified"))
      (node (ref "C39") (pin "1") (pinfunction "1_1") (pintype "unspecified"))
      (node (ref "C4") (pin "2") (pinfunction "2_2") (pintype "unspecified"))
      (node (ref "C40") (pin "1") (pinfunction "1_1") (pintype "unspecified"))
      (node (ref "C41") (pin "1") (pinfunction "1_1") (pintype "unspecified"))
      (node (ref "C42") (pin "1") (pinfunction "1_1") (pintype "unspecified"))
      (node (ref "C43") (pin "1") (pinfunction "1_1") (pintype "unspecified"))
      (node (ref "C5") (pin "2") (pinfunction "2_2") (pintype "unspecified"))
      (node (ref "C6") (pin "2") (pinfunction "2_2") (pintype "unspecified"))
      (node (ref "C7") (pin "2") (pinfunction "2_2") (pintype "unspecified"))
      (node (ref "C8") (pin "2") (pinfunction "2_2") (pintype "unspecified"))
      (node (ref "C9") (pin "2") (pinfunction "2_2") (pintype "unspecified"))
      (node (ref "CN1") (pin "1") (pinfunction "-_1") (pintype "unspecified"))
      (node (ref "CN2") (pin "2") (pinfunction "-_2") (pintype "unspecified"))
      (node (ref "D1") (pin "1") (pinfunction "1_1") (pintype "unspecified"))
      (node (ref "D2") (pin "2") (pinfunction "A_2") (pintype "unspecified"))
      (node (ref "LED1") (pin "2") (pinfunction "K_2") (pintype "unspecified"))
      (node (ref "R3") (pin "1") (pinfunction "1_1") (pintype "unspecified"))
      (node (ref "R7") (pin "2") (pinfunction "2_2") (pintype "unspecified"))
      (node (ref "U1") (pin "2") (pinfunction "2_2") (pintype "unspecified"))
      (node (ref "U2") (pin "2") (pinfunction "2_2") (pintype "input"))
      (node (ref "U3") (pin "2") (pinfunction "2_2") (pintype "unspecified"))
      (node (ref "U4") (pin "6") (pinfunction "GND_6") (pintype "unspecified"))
      (node (ref "U4") (pin "9") (pinfunction "PowerPAD_9") (pintype "unspecified"))
      (node (ref "U5") (pin "2") (pinfunction "-VIN_2") (pintype "unspecified"))
      (node (ref "U5") (pin "5") (pinfunction "-VO_5") (pintype "unspecified"))
      (node (ref "U6") (pin "1") (pinfunction "PGND2_1") (pintype "unspecified"))
      (node (ref "U6") (pin "15") (pinfunction "PGND1_15") (pintype "unspecified"))
    )
    (net (code "7") (name "Net-(CN1-+)") (class "Default")
      (node (ref "CN1") (pin "2") (pinfunction "+_2") (pintype "unspecified"))
      (node (ref "F1") (pin "1") (pinfunction "1_1") (pintype "unspecified"))
    )
    (net (code "8") (name "Net-(D2-K)") (class "Default")
      (node (ref "C2") (pin "2") (pinfunction "2_2") (pintype "input"))
      (node (ref "D2") (pin "1") (pinfunction "K_1") (pintype "unspecified"))
      (node (ref "L1") (pin "1") (pinfunction "1_1") (pintype "unspecified"))
      (node (ref "U4") (pin "8") (pinfunction "PH_8") (pintype "unspecified"))
    )
    (net (code "9") (name "Net-(LED1-A)") (class "Default")
      (node (ref "LED1") (pin "1") (pinfunction "A_1") (pintype "unspecified"))
      (node (ref "R1") (pin "2") (pinfunction "2_2") (pintype "unspecified"))
    )
    (net (code "10") (name "Net-(U4-BOOT)") (class "Default")
      (node (ref "C2") (pin "1") (pinfunction "1_1") (pintype "input"))
      (node (ref "U4") (pin "1") (pinfunction "BOOT_1") (pintype "unspecified"))
    )
    (net (code "11") (name "Net-(U4-VSENSE)") (class "Default")
      (node (ref "R2") (pin "1") (pinfunction "1_1") (pintype "input"))
      (node (ref "R3") (pin "2") (pinfunction "2_2") (pintype "unspecified"))
      (node (ref "U4") (pin "4") (pinfunction "VSENSE_4") (pintype "unspecified"))
    )
    (net (code "12") (name "Net-(U6-CBOOT)") (class "Default")
      (node (ref "C33") (pin "1") (pinfunction "1_1") (pintype "unspecified"))
      (node (ref "U6") (pin "3") (pinfunction "RBOOT_3") (pintype "unspecified"))
      (node (ref "U6") (pin "4") (pinfunction "CBOOT_4") (pintype "unspecified"))
    )
    (net (code "13") (name "Net-(U6-FB)") (class "Default")
      (node (ref "R4") (pin "1") (pinfunction "1_1") (pintype "unspecified"))
      (node (ref "R5") (pin "2") (pinfunction "2_2") (pintype "input"))
      (node (ref "U6") (pin "7") (pinfunction "FB_7") (pintype "unspecified"))
    )
    (net (code "14") (name "Net-(U6-RESET#)") (class "Default")
      (node (ref "R6") (pin "1") (pinfunction "1_1") (pintype "input"))
      (node (ref "U6") (pin "10") (pinfunction "RESET#_10") (pintype "unspecified"))
    )
    (net (code "15") (name "Net-(U6-RT)") (class "Default")
      (node (ref "C44") (pin "2") (pinfunction "2_2") (pintype "unspecified"))
      (node (ref "U6") (pin "6") (pinfunction "VCC_6") (pintype "unspecified"))
      (node (ref "U6") (pin "9") (pinfunction "RT_9") (pintype "unspecified"))
    )
    (net (code "16") (name "Net-(U6-SW)") (class "Default")
      (node (ref "C33") (pin "2") (pinfunction "2_2") (pintype "unspecified"))
      (node (ref "U6") (pin "16") (pinfunction "SW_16") (pintype "unspecified"))
      (node (ref "U7") (pin "1") (pinfunction "1_1") (pintype "unspecified"))
    )
    (net (code "17") (name "unconnected-(CN1-Pad3)") (class "Default")
      (node (ref "CN1") (pin "3") (pinfunction "3_3") (pintype "unspecified+no_connect"))
    )
    (net (code "18") (name "unconnected-(CN1-Pad4)") (class "Default")
      (node (ref "CN1") (pin "4") (pinfunction "4_4") (pintype "unspecified+no_connect"))
    )
    (net (code "19") (name "unconnected-(SCREW1-Pad1)") (class "Default")
      (node (ref "SCREW1") (pin "1") (pinfunction "1_1") (pintype "input+no_connect"))
    )
    (net (code "20") (name "unconnected-(SCREW2-Pad1)") (class "Default")
      (node (ref "SCREW2") (pin "1") (pinfunction "1_1") (pintype "input+no_connect"))
    )
    (net (code "21") (name "unconnected-(SCREW3-Pad1)") (class "Default")
      (node (ref "SCREW3") (pin "1") (pinfunction "1_1") (pintype "input+no_connect"))
    )
    (net (code "22") (name "unconnected-(U1-Pad3)") (class "Default")
      (node (ref "U1") (pin "3") (pinfunction "3_3") (pintype "unspecified+no_connect"))
    )
    (net (code "23") (name "unconnected-(U1-Pad4)") (class "Default")
      (node (ref "U1") (pin "4") (pinfunction "4_4") (pintype "unspecified+no_connect"))
    )
    (net (code "24") (name "unconnected-(U3-Pad3)") (class "Default")
      (node (ref "U3") (pin "3") (pinfunction "3_3") (pintype "unspecified+no_connect"))
    )
    (net (code "25") (name "unconnected-(U3-Pad4)") (class "Default")
      (node (ref "U3") (pin "4") (pinfunction "4_4") (pintype "unspecified+no_connect"))
    )
    (net (code "26") (name "unconnected-(U4-ENA-Pad5)") (class "Default")
      (node (ref "U4") (pin "5") (pinfunction "ENA_5") (pintype "unspecified+no_connect"))
    )
    (net (code "27") (name "unconnected-(U4-NC-Pad2)") (class "Default")
      (node (ref "U4") (pin "2") (pinfunction "NC_2") (pintype "unspecified+no_connect"))
    )
    (net (code "28") (name "unconnected-(U4-NC-Pad3)") (class "Default")
      (node (ref "U4") (pin "3") (pinfunction "NC_3") (pintype "unspecified+no_connect"))
    )
    (net (code "29") (name "unconnected-(U5-CTRL-Pad3)") (class "Default")
      (node (ref "U5") (pin "3") (pinfunction "CTRL_3") (pintype "unspecified+no_connect"))
    )
    (net (code "30") (name "unconnected-(U5-TRIM-Pad4)") (class "Default")
      (node (ref "U5") (pin "4") (pinfunction "TRIM_4") (pintype "unspecified+no_connect"))
    )
  )
)
